# IPS-LCD-1_14.net
KiCad netlist of a schematic drawn in Altium Designer
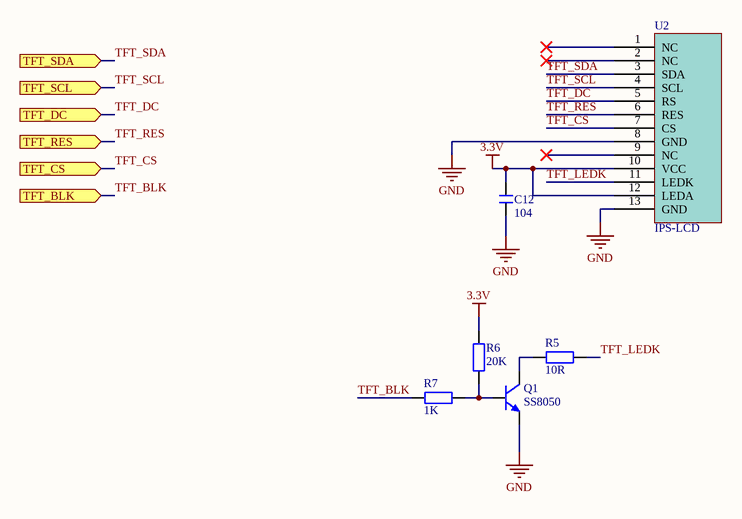
[diagram p0: IPS-LCD-1.14寸裸屏模块.SchDoc]

(export (version "E")
  (design (tool "Eeschema 10.0.6"))
  (components
    (comp (ref "C12")
      (value "104")
      (footprint "C 0603_L")
      (description "无极性贴片电容")
      (fields (field (name "版权归属") "黎明电子style"))
      (libsource (lib "3.3   - 电容capacitor") (part "C"))
    )
    (comp (ref "Q1")
      (value "SS8050")
      (footprint "SOT23-3N")
      (description "高频放大-NPN型 丝印J3Y")
      (fields (field (name "版权归属") "源创客"))
      (libsource (lib "6.2   - 三极管") (part "8050-SMD"))
    )
    (comp (ref "R5")
      (value "10R")
      (footprint "R 0603_L")
      (description "贴片电阻")
      (fields (field (name "版权归属") "黎明电子style"))
      (libsource (lib "3.4   - 电阻Resistor") (part "R"))
    )
    (comp (ref "R6")
      (value "20K")
      (footprint "R 0603_L")
      (description "贴片电阻")
      (fields (field (name "版权归属") "黎明电子style"))
      (libsource (lib "3.4   - 电阻Resistor") (part "R"))
    )
    (comp (ref "R7")
      (value "1K")
      (footprint "R 0603_L")
      (description "贴片电阻")
      (fields (field (name "版权归属") "黎明电子style"))
      (libsource (lib "3.4   - 电阻Resistor") (part "R"))
    )
    (comp (ref "U2")
      (value "IPS-LCD")
      (footprint "1.14IPS-LCD")
      (description "IPS-LCD-1.14寸裸屏spi接口")
      (libsource (lib "9.2   - 显示器件") (part "IPS-LCD-1.14"))
    )
  )
  (nets
    (net (code "1") (name "/TFT_BLK") (class "Default")
      (node (ref "R7") (pin "1") (pinfunction "1_1") (pintype "passive"))
    )
    (net (code "2") (name "/TFT_CS") (class "Default")
      (node (ref "U2") (pin "7") (pinfunction "CS_7") (pintype "passive"))
    )
    (net (code "3") (name "/TFT_DC") (class "Default")
      (node (ref "U2") (pin "5") (pinfunction "RS_5") (pintype "passive"))
    )
    (net (code "4") (name "/TFT_LEDK") (class "Default")
      (node (ref "R5") (pin "1") (pinfunction "1_1") (pintype "passive"))
      (node (ref "U2") (pin "11") (pinfunction "LEDK_11") (pintype "passive"))
    )
    (net (code "5") (name "/TFT_RES") (class "Default")
      (node (ref "U2") (pin "6") (pinfunction "RES_6") (pintype "passive"))
    )
    (net (code "6") (name "/TFT_SCL") (class "Default")
      (node (ref "U2") (pin "4") (pinfunction "SCL_4") (pintype "passive"))
    )
    (net (code "7") (name "/TFT_SDA") (class "Default")
      (node (ref "U2") (pin "3") (pinfunction "SDA_3") (pintype "passive"))
    )
    (net (code "8") (name "3.3V") (class "Default")
      (node (ref "C12") (pin "1") (pinfunction "1_1") (pintype "passive"))
      (node (ref "R6") (pin "2") (pinfunction "2_2") (pintype "passive"))
      (node (ref "U2") (pin "10") (pinfunction "VCC_10") (pintype "passive"))
      (node (ref "U2") (pin "12") (pinfunction "LEDA_12") (pintype "passive"))
    )
    (net (code "9") (name "GND") (class "Default")
      (node (ref "C12") (pin "2") (pinfunction "2_2") (pintype "passive"))
      (node (ref "Q1") (pin "2") (pinfunction "E_2") (pintype "passive"))
      (node (ref "U2") (pin "13") (pinfunction "GND_13") (pintype "passive"))
      (node (ref "U2") (pin "8") (pinfunction "GND_8") (pintype "passive"))
    )
    (net (code "10") (name "Net-(Q1-B)") (class "Default")
      (node (ref "Q1") (pin "1") (pinfunction "B_1") (pintype "passive"))
      (node (ref "R6") (pin "1") (pinfunction "1_1") (pintype "passive"))
      (node (ref "R7") (pin "2") (pinfunction "2_2") (pintype "passive"))
    )
    (net (code "11") (name "Net-(Q1-C)") (class "Default")
      (node (ref "Q1") (pin "3") (pinfunction "C_3") (pintype "passive"))
      (node (ref "R5") (pin "2") (pinfunction "2_2") (pintype "passive"))
    )
    (net (code "12") (name "unconnected-(U2-NC-Pad1)") (class "Default")
      (node (ref "U2") (pin "1") (pinfunction "NC_1") (pintype "passive+no_connect"))
    )
    (net (code "13") (name "unconnected-(U2-NC-Pad2)") (class "Default")
      (node (ref "U2") (pin "2") (pinfunction "NC_2") (pintype "passive+no_connect"))
    )
    (net (code "14") (name "unconnected-(U2-NC-Pad9)") (class "Default")
      (node (ref "U2") (pin "9") (pinfunction "NC_9") (pintype "passive+no_connect"))
    )
  )
)
